# base_board.net
KiCad netlist of a schematic drawn in Altium Designer
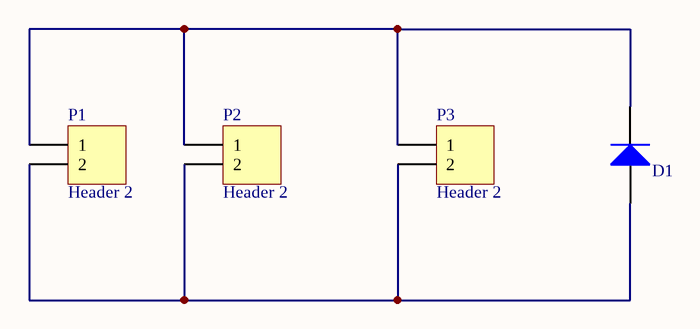
[diagram p0: base_board.SchDoc]

(export (version "E")
  (design (tool "Eeschema 10.0.6"))
  (components
    (comp (ref "D1") (value "D Diode") (footprint "0805_M_POL") (libsource (lib "UNSW_LIB") (part "D Diode")))
    (comp (ref "P1")
      (value "Header 2")
      (footprint "HDR1X2")
      (description "Header, 2-Pin")
      (fields (field (name "PUBLISHER") "Altium Limited"))
      (libsource (lib "Miscellaneous Connectors") (part "Header 2"))
    )
    (comp (ref "P2")
      (value "Header 2")
      (footprint "HDR1X2")
      (description "Header, 2-Pin")
      (fields (field (name "PUBLISHER") "Altium Limited"))
      (libsource (lib "Miscellaneous Connectors") (part "Header 2"))
    )
    (comp (ref "P3")
      (value "Header 2")
      (footprint "HDR1X2")
      (description "Header, 2-Pin")
      (fields (field (name "PUBLISHER") "Altium Limited"))
      (libsource (lib "Miscellaneous Connectors") (part "Header 2"))
    )
  )
  (nets
    (net (code "1") (name "Net-(D1-A)") (class "Default")
      (node (ref "D1") (pin "1") (pinfunction "A_1") (pintype "passive"))
      (node (ref "P1") (pin "2") (pinfunction "2_2") (pintype "passive"))
      (node (ref "P2") (pin "2") (pinfunction "2_2") (pintype "passive"))
      (node (ref "P3") (pin "2") (pinfunction "2_2") (pintype "passive"))
    )
    (net (code "2") (name "Net-(D1-K)") (class "Default")
      (node (ref "D1") (pin "2") (pinfunction "K_2") (pintype "passive"))
      (node (ref "P1") (pin "1") (pinfunction "1_1") (pintype "passive"))
      (node (ref "P2") (pin "1") (pinfunction "1_1") (pintype "passive"))
      (node (ref "P3") (pin "1") (pinfunction "1_1") (pintype "passive"))
    )
  )
)
